# FiberLink.net
KiCad netlist of a schematic drawn in EAGLE
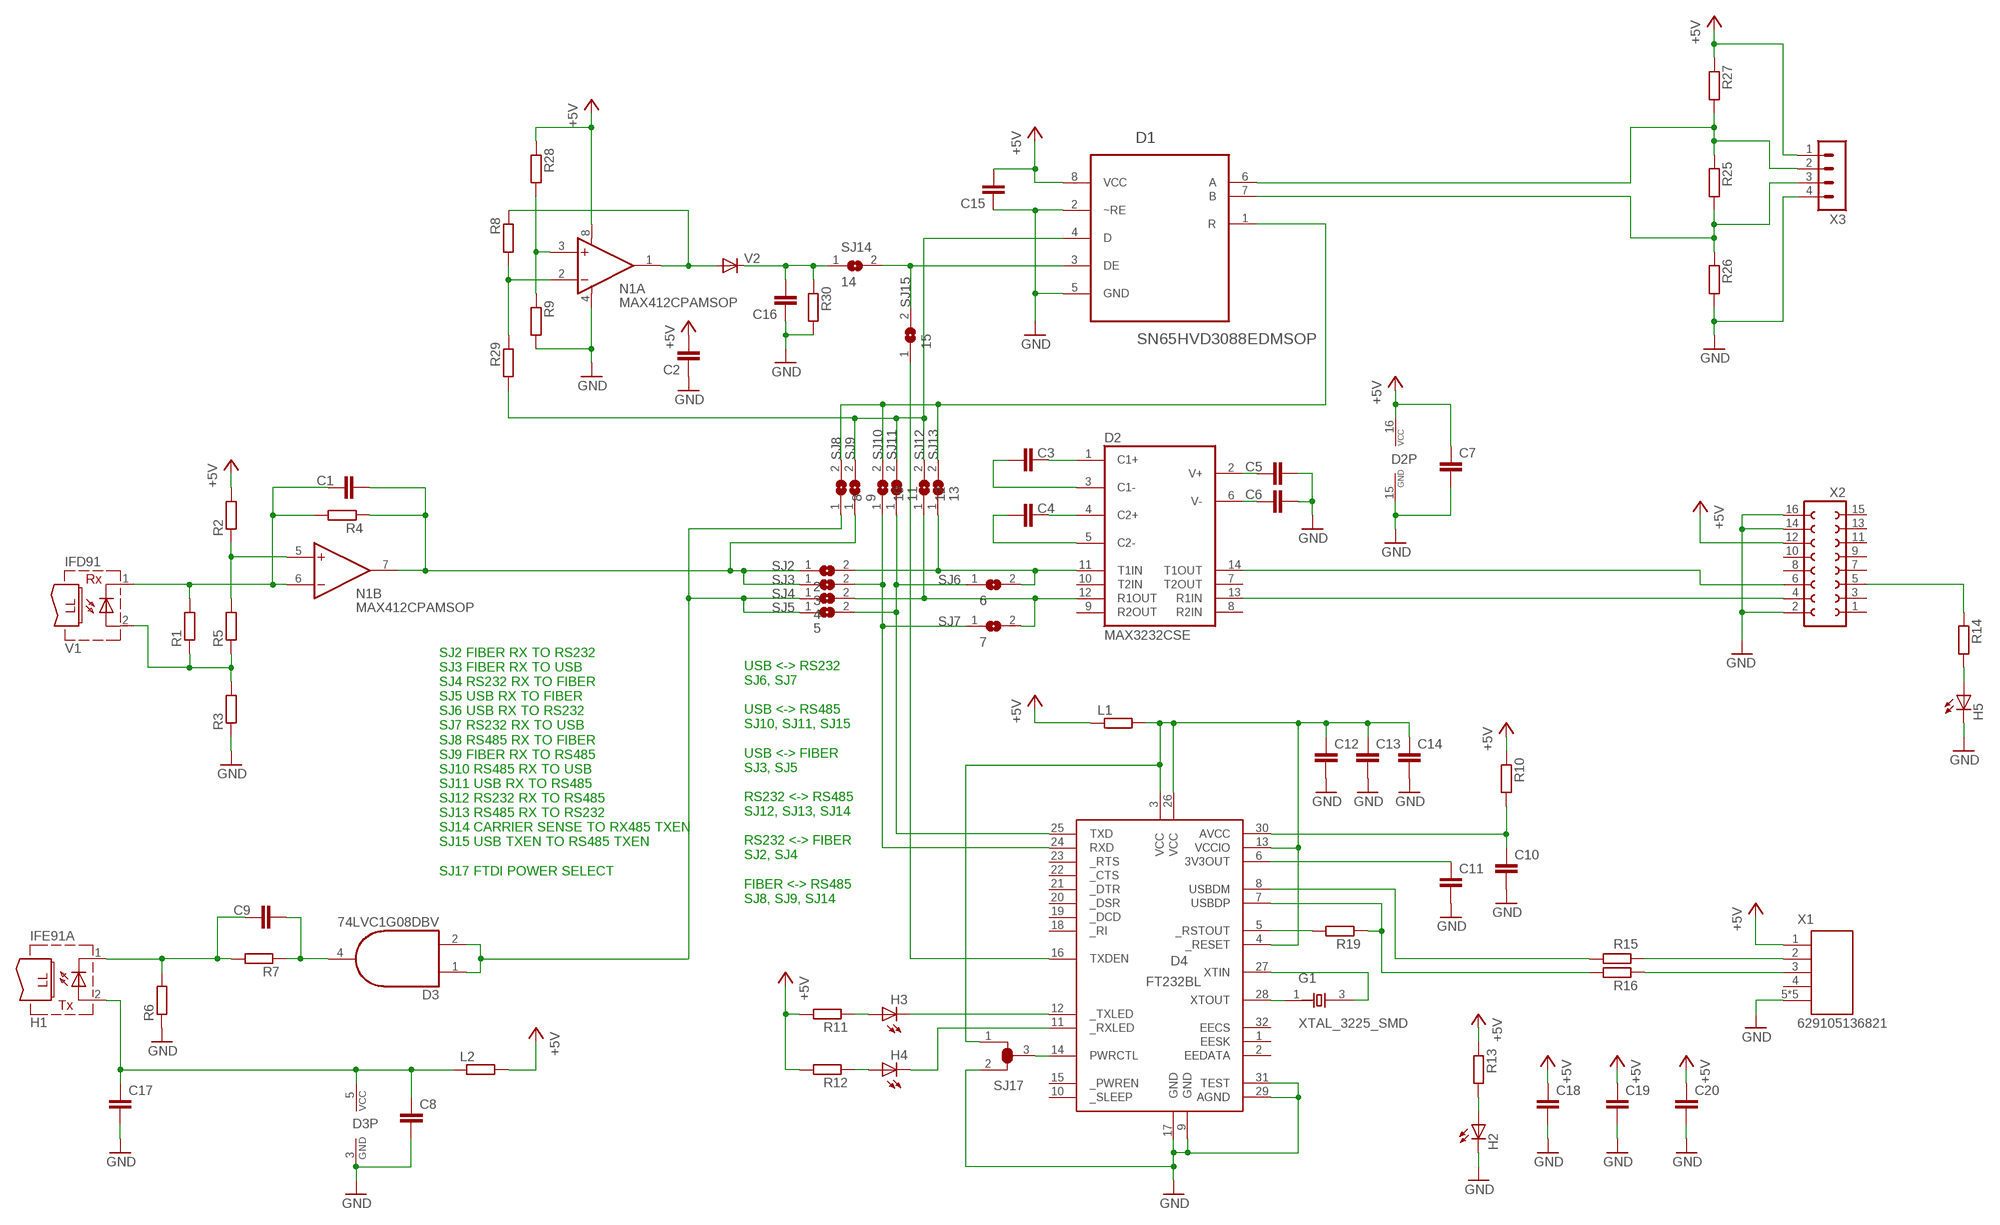
[diagram p0: schematic, sheet 1]

(export (version "E")
  (design (tool "Eeschema 10.0.6"))
  (components
    (comp (ref "C1")
      (value "C-EUC0402")
      (footprint "eagle-import:C0402")
      (libsource (lib "eagle-import") (part "C-EUC0402"))
    )
    (comp (ref "C2")
      (value "C-EUC0402")
      (footprint "eagle-import:C0402")
      (libsource (lib "eagle-import") (part "C-EUC0402"))
    )
    (comp (ref "C3")
      (value "C-EUC0402")
      (footprint "eagle-import:C0402")
      (libsource (lib "eagle-import") (part "C-EUC0402"))
    )
    (comp (ref "C4")
      (value "C-EUC0402")
      (footprint "eagle-import:C0402")
      (libsource (lib "eagle-import") (part "C-EUC0402"))
    )
    (comp (ref "C5")
      (value "C-EUC0402")
      (footprint "eagle-import:C0402")
      (libsource (lib "eagle-import") (part "C-EUC0402"))
    )
    (comp (ref "C6")
      (value "C-EUC0402")
      (footprint "eagle-import:C0402")
      (libsource (lib "eagle-import") (part "C-EUC0402"))
    )
    (comp (ref "C7")
      (value "C-EUC0402")
      (footprint "eagle-import:C0402")
      (libsource (lib "eagle-import") (part "C-EUC0402"))
    )
    (comp (ref "C8")
      (value "C-EUC0402")
      (footprint "eagle-import:C0402")
      (libsource (lib "eagle-import") (part "C-EUC0402"))
    )
    (comp (ref "C9")
      (value "C-EUC0402")
      (footprint "eagle-import:C0402")
      (libsource (lib "eagle-import") (part "C-EUC0402"))
    )
    (comp (ref "C10")
      (value "C-EUC0402")
      (footprint "eagle-import:C0402")
      (libsource (lib "eagle-import") (part "C-EUC0402"))
    )
    (comp (ref "C11")
      (value "C-EUC0402")
      (footprint "eagle-import:C0402")
      (libsource (lib "eagle-import") (part "C-EUC0402"))
    )
    (comp (ref "C12")
      (value "C-EUC0402")
      (footprint "eagle-import:C0402")
      (libsource (lib "eagle-import") (part "C-EUC0402"))
    )
    (comp (ref "C13")
      (value "C-EUC0402")
      (footprint "eagle-import:C0402")
      (libsource (lib "eagle-import") (part "C-EUC0402"))
    )
    (comp (ref "C14")
      (value "C-EUC0402")
      (footprint "eagle-import:C0402")
      (libsource (lib "eagle-import") (part "C-EUC0402"))
    )
    (comp (ref "C15")
      (value "C-EUC0402")
      (footprint "eagle-import:C0402")
      (libsource (lib "eagle-import") (part "C-EUC0402"))
    )
    (comp (ref "C16")
      (value "C-EUC0402")
      (footprint "eagle-import:C0402")
      (libsource (lib "eagle-import") (part "C-EUC0402"))
    )
    (comp (ref "C17")
      (value "C-EUC0402")
      (footprint "eagle-import:C0402")
      (libsource (lib "eagle-import") (part "C-EUC0402"))
    )
    (comp (ref "C18")
      (value "C-EUC0805")
      (footprint "eagle-import:C0805")
      (libsource (lib "eagle-import") (part "C-EUC0805"))
    )
    (comp (ref "C19")
      (value "C-EUC0805")
      (footprint "eagle-import:C0805")
      (libsource (lib "eagle-import") (part "C-EUC0805"))
    )
    (comp (ref "C20")
      (value "C-EUC0805")
      (footprint "eagle-import:C0805")
      (libsource (lib "eagle-import") (part "C-EUC0805"))
    )
    (comp (ref "D1")
      (value "SN65HVD3088EDMSOP")
      (footprint "eagle-import:SOP65P490X110-8N")
      (libsource (lib "eagle-import") (part "SN65HVD3088EDMSOP"))
    )
    (comp (ref "D2")
      (value "MAX3232CSE")
      (footprint "eagle-import:SO16")
      (libsource (lib "eagle-import") (part "MAX3232SEC"))
    )
    (comp (ref "D3")
      (value "74LVC1G08DBV")
      (footprint "eagle-import:SOT23-5")
      (libsource (lib "eagle-import") (part "741G08DBVLVC"))
    )
    (comp (ref "D4")
      (value "FT232BL")
      (footprint "eagle-import:LQFP32")
      (libsource (lib "eagle-import") (part "FT232BL"))
    )
    (comp (ref "G1")
      (value "XTAL_3225_SMD")
      (footprint "eagle-import:X_3225")
      (libsource (lib "eagle-import") (part "XTAL_3225_SMD"))
    )
    (comp (ref "H1")
      (value "IFE91A")
      (footprint "eagle-import:IFO-IFX")
      (libsource (lib "eagle-import") (part "IFE91A"))
    )
    (comp (ref "H2")
      (value "LEDCHIP-LED0603")
      (footprint "eagle-import:CHIP-LED0603")
      (libsource (lib "eagle-import") (part "LEDCHIP-LED0603"))
    )
    (comp (ref "H3")
      (value "LEDCHIP-LED0603")
      (footprint "eagle-import:CHIP-LED0603")
      (libsource (lib "eagle-import") (part "LEDCHIP-LED0603"))
    )
    (comp (ref "H4")
      (value "LEDCHIP-LED0603")
      (footprint "eagle-import:CHIP-LED0603")
      (libsource (lib "eagle-import") (part "LEDCHIP-LED0603"))
    )
    (comp (ref "H5")
      (value "LEDCHIP-LED0603")
      (footprint "eagle-import:CHIP-LED0603")
      (libsource (lib "eagle-import") (part "LEDCHIP-LED0603"))
    )
    (comp (ref "L1")
      (value "R-EU_R0402")
      (footprint "eagle-import:R0402_VISHAY")
      (libsource (lib "eagle-import") (part "R-EU_R0402"))
    )
    (comp (ref "L2")
      (value "R-EU_R0402")
      (footprint "eagle-import:R0402_VISHAY")
      (libsource (lib "eagle-import") (part "R-EU_R0402"))
    )
    (comp (ref "N1")
      (value "MAX412CPAMSOP")
      (footprint "eagle-import:SOP65P490X110-8N")
      (libsource (lib "eagle-import") (part "MAX412CPAMSOP"))
    )
    (comp (ref "R1")
      (value "R-EU_R0402")
      (footprint "eagle-import:R0402_VISHAY")
      (libsource (lib "eagle-import") (part "R-EU_R0402"))
    )
    (comp (ref "R2")
      (value "R-EU_R0402")
      (footprint "eagle-import:R0402_VISHAY")
      (libsource (lib "eagle-import") (part "R-EU_R0402"))
    )
    (comp (ref "R3")
      (value "R-EU_R0402")
      (footprint "eagle-import:R0402_VISHAY")
      (libsource (lib "eagle-import") (part "R-EU_R0402"))
    )
    (comp (ref "R4")
      (value "R-EU_R0402")
      (footprint "eagle-import:R0402_VISHAY")
      (libsource (lib "eagle-import") (part "R-EU_R0402"))
    )
    (comp (ref "R5")
      (value "R-EU_R0402")
      (footprint "eagle-import:R0402_VISHAY")
      (libsource (lib "eagle-import") (part "R-EU_R0402"))
    )
    (comp (ref "R6")
      (value "R-EU_R1206")
      (footprint "eagle-import:R1206")
      (libsource (lib "eagle-import") (part "R-EU_R1206"))
    )
    (comp (ref "R7")
      (value "R-EU_R1206")
      (footprint "eagle-import:R1206")
      (libsource (lib "eagle-import") (part "R-EU_R1206"))
    )
    (comp (ref "R8")
      (value "R-EU_R0402")
      (footprint "eagle-import:R0402_VISHAY")
      (libsource (lib "eagle-import") (part "R-EU_R0402"))
    )
    (comp (ref "R9")
      (value "R-EU_R0402")
      (footprint "eagle-import:R0402_VISHAY")
      (libsource (lib "eagle-import") (part "R-EU_R0402"))
    )
    (comp (ref "R10")
      (value "R-EU_R0402")
      (footprint "eagle-import:R0402_VISHAY")
      (libsource (lib "eagle-import") (part "R-EU_R0402"))
    )
    (comp (ref "R11")
      (value "R-EU_R0402")
      (footprint "eagle-import:R0402_VISHAY")
      (libsource (lib "eagle-import") (part "R-EU_R0402"))
    )
    (comp (ref "R12")
      (value "R-EU_R0402")
      (footprint "eagle-import:R0402_VISHAY")
      (libsource (lib "eagle-import") (part "R-EU_R0402"))
    )
    (comp (ref "R13")
      (value "R-EU_R0402")
      (footprint "eagle-import:R0402_VISHAY")
      (libsource (lib "eagle-import") (part "R-EU_R0402"))
    )
    (comp (ref "R14")
      (value "R-EU_R0402")
      (footprint "eagle-import:R0402_VISHAY")
      (libsource (lib "eagle-import") (part "R-EU_R0402"))
    )
    (comp (ref "R15")
      (value "R-EU_R0402")
      (footprint "eagle-import:R0402_VISHAY")
      (libsource (lib "eagle-import") (part "R-EU_R0402"))
    )
    (comp (ref "R16")
      (value "R-EU_R0402")
      (footprint "eagle-import:R0402_VISHAY")
      (libsource (lib "eagle-import") (part "R-EU_R0402"))
    )
    (comp (ref "R19")
      (value "R-EU_R0402")
      (footprint "eagle-import:R0402_VISHAY")
      (libsource (lib "eagle-import") (part "R-EU_R0402"))
    )
    (comp (ref "R25")
      (value "R-EU_R1206")
      (footprint "eagle-import:R1206")
      (libsource (lib "eagle-import") (part "R-EU_R1206"))
    )
    (comp (ref "R26")
      (value "R-EU_R0603")
      (footprint "eagle-import:R0603")
      (libsource (lib "eagle-import") (part "R-EU_R0603"))
    )
    (comp (ref "R27")
      (value "R-EU_R0603")
      (footprint "eagle-import:R0603")
      (libsource (lib "eagle-import") (part "R-EU_R0603"))
    )
    (comp (ref "R28")
      (value "R-EU_R0402")
      (footprint "eagle-import:R0402_VISHAY")
      (libsource (lib "eagle-import") (part "R-EU_R0402"))
    )
    (comp (ref "R29")
      (value "R-EU_R0402")
      (footprint "eagle-import:R0402_VISHAY")
      (libsource (lib "eagle-import") (part "R-EU_R0402"))
    )
    (comp (ref "R30")
      (value "R-EU_R0402")
      (footprint "eagle-import:R0402_VISHAY")
      (libsource (lib "eagle-import") (part "R-EU_R0402"))
    )
    (comp (ref "SJ2")
      (value "2")
      (footprint "eagle-import:SJ-SMALL")
      (libsource (lib "eagle-import") (part "SJ"))
    )
    (comp (ref "SJ3")
      (value "3")
      (footprint "eagle-import:SJ-SMALL")
      (libsource (lib "eagle-import") (part "SJ"))
    )
    (comp (ref "SJ4")
      (value "4")
      (footprint "eagle-import:SJ-SMALL")
      (libsource (lib "eagle-import") (part "SJ"))
    )
    (comp (ref "SJ5")
      (value "5")
      (footprint "eagle-import:SJ-SMALL")
      (libsource (lib "eagle-import") (part "SJ"))
    )
    (comp (ref "SJ6")
      (value "6")
      (footprint "eagle-import:SJ-SMALL")
      (libsource (lib "eagle-import") (part "SJ"))
    )
    (comp (ref "SJ7")
      (value "7")
      (footprint "eagle-import:SJ-SMALL")
      (libsource (lib "eagle-import") (part "SJ"))
    )
    (comp (ref "SJ8")
      (value "8")
      (footprint "eagle-import:SJ-SMALL")
      (libsource (lib "eagle-import") (part "SJ"))
    )
    (comp (ref "SJ9")
      (value "9")
      (footprint "eagle-import:SJ-SMALL")
      (libsource (lib "eagle-import") (part "SJ"))
    )
    (comp (ref "SJ10")
      (value "10")
      (footprint "eagle-import:SJ-SMALL")
      (libsource (lib "eagle-import") (part "SJ"))
    )
    (comp (ref "SJ11")
      (value "11")
      (footprint "eagle-import:SJ-SMALL")
      (libsource (lib "eagle-import") (part "SJ"))
    )
    (comp (ref "SJ12")
      (value "12")
      (footprint "eagle-import:SJ-SMALL")
      (libsource (lib "eagle-import") (part "SJ"))
    )
    (comp (ref "SJ13")
      (value "13")
      (footprint "eagle-import:SJ-SMALL")
      (libsource (lib "eagle-import") (part "SJ"))
    )
    (comp (ref "SJ14")
      (value "14")
      (footprint "eagle-import:SJ-SMALL")
      (libsource (lib "eagle-import") (part "SJ"))
    )
    (comp (ref "SJ15")
      (value "15")
      (footprint "eagle-import:SJ-SMALL")
      (libsource (lib "eagle-import") (part "SJ"))
    )
    (comp (ref "SJ17")
      (value "17")
      (footprint "eagle-import:SJ-SMALL-TRI")
      (libsource (lib "eagle-import") (part "SJ-TRI"))
    )
    (comp (ref "V1")
      (value "IFD91")
      (footprint "eagle-import:IFO-IFX")
      (libsource (lib "eagle-import") (part "IFD91"))
    )
    (comp (ref "V2")
      (value "DIODE-SOD323-R")
      (footprint "eagle-import:SOD323-R")
      (libsource (lib "eagle-import") (part "DIODE-SOD323-R"))
    )
    (comp (ref "X1")
      (value "629105136821")
      (footprint "eagle-import:629105136821")
      (libsource (lib "eagle-import") (part "629105136821"))
    )
    (comp (ref "X2")
      (value "FE08-2")
      (footprint "eagle-import:FE08-2")
      (libsource (lib "eagle-import") (part "FE08-2"))
    )
    (comp (ref "X3")
      (value "MA04-1")
      (footprint "eagle-import:MA04-1")
      (libsource (lib "eagle-import") (part "MA04-1"))
    )
  )
  (nets
    (net (code "1") (name "+5V") (class "Default")
      (node (ref "C15") (pin "2") (pinfunction "2_2") (pintype "passive"))
      (node (ref "C18") (pin "1") (pinfunction "1_1") (pintype "passive"))
      (node (ref "C19") (pin "1") (pinfunction "1_1") (pintype "passive"))
      (node (ref "C2") (pin "2") (pinfunction "2_2") (pintype "passive"))
      (node (ref "C20") (pin "1") (pinfunction "1_1") (pintype "passive"))
      (node (ref "C7") (pin "1") (pinfunction "1_1") (pintype "passive"))
      (node (ref "D1") (pin "8") (pinfunction "VCC_8") (pintype "power_in"))
      (node (ref "D2") (pin "16") (pinfunction "VCC_16") (pintype "power_in"))
      (node (ref "L1") (pin "1") (pinfunction "1_1") (pintype "passive"))
      (node (ref "L2") (pin "2") (pinfunction "2_2") (pintype "passive"))
      (node (ref "N1") (pin "8") (pinfunction "V+_8") (pintype "power_in"))
      (node (ref "R10") (pin "1") (pinfunction "1_1") (pintype "passive"))
      (node (ref "R11") (pin "2") (pinfunction "2_2") (pintype "passive"))
      (node (ref "R12") (pin "2") (pinfunction "2_2") (pintype "passive"))
      (node (ref "R13") (pin "1") (pinfunction "1_1") (pintype "passive"))
      (node (ref "R2") (pin "2") (pinfunction "2_2") (pintype "passive"))
      (node (ref "R27") (pin "1") (pinfunction "1_1") (pintype "passive"))
      (node (ref "R28") (pin "1") (pinfunction "1_1") (pintype "passive"))
      (node (ref "X1") (pin "1") (pinfunction "1_1") (pintype "passive"))
      (node (ref "X2") (pin "12") (pinfunction "12_12") (pintype "passive"))
      (node (ref "X3") (pin "1") (pinfunction "1_1") (pintype "passive"))
    )
    (net (code "2") (name "GND") (class "Default")
      (node (ref "C10") (pin "2") (pinfunction "2_2") (pintype "passive"))
      (node (ref "C11") (pin "2") (pinfunction "2_2") (pintype "passive"))
      (node (ref "C12") (pin "2") (pinfunction "2_2") (pintype "passive"))
      (node (ref "C13") (pin "2") (pinfunction "2_2") (pintype "passive"))
      (node (ref "C14") (pin "2") (pinfunction "2_2") (pintype "passive"))
      (node (ref "C15") (pin "1") (pinfunction "1_1") (pintype "passive"))
      (node (ref "C16") (pin "1") (pinfunction "1_1") (pintype "passive"))
      (node (ref "C17") (pin "2") (pinfunction "2_2") (pintype "passive"))
      (node (ref "C18") (pin "2") (pinfunction "2_2") (pintype "passive"))
      (node (ref "C19") (pin "2") (pinfunction "2_2") (pintype "passive"))
      (node (ref "C2") (pin "1") (pinfunction "1_1") (pintype "passive"))
      (node (ref "C20") (pin "2") (pinfunction "2_2") (pintype "passive"))
      (node (ref "C5") (pin "2") (pinfunction "2_2") (pintype "passive"))
      (node (ref "C6") (pin "2") (pinfunction "2_2") (pintype "passive"))
      (node (ref "C7") (pin "2") (pinfunction "2_2") (pintype "passive"))
      (node (ref "C8") (pin "2") (pinfunction "2_2") (pintype "passive"))
      (node (ref "D1") (pin "2") (pinfunction "~{RE}_2") (pintype "input"))
      (node (ref "D1") (pin "5") (pinfunction "GND_5") (pintype "passive"))
      (node (ref "D2") (pin "15") (pinfunction "GND_15") (pintype "power_in"))
      (node (ref "D3") (pin "3") (pinfunction "GND_3") (pintype "power_in"))
      (node (ref "D4") (pin "17") (pinfunction "GND_17") (pintype "power_in"))
      (node (ref "D4") (pin "29") (pinfunction "AGND_29") (pintype "power_in"))
      (node (ref "D4") (pin "31") (pinfunction "TEST_31") (pintype "input"))
      (node (ref "D4") (pin "9") (pinfunction "GND_9") (pintype "power_in"))
      (node (ref "H2") (pin "C") (pinfunction "C_C") (pintype "passive"))
      (node (ref "H5") (pin "C") (pinfunction "C_C") (pintype "passive"))
      (node (ref "N1") (pin "4") (pinfunction "V-_4") (pintype "power_in"))
      (node (ref "R26") (pin "2") (pinfunction "2_2") (pintype "passive"))
      (node (ref "R3") (pin "1") (pinfunction "1_1") (pintype "passive"))
      (node (ref "R30") (pin "2") (pinfunction "2_2") (pintype "passive"))
      (node (ref "R6") (pin "1") (pinfunction "1_1") (pintype "passive"))
      (node (ref "R9") (pin "2") (pinfunction "2_2") (pintype "passive"))
      (node (ref "SJ17") (pin "2") (pinfunction "2_2") (pintype "passive"))
      (node (ref "X1") (pin "5") (pinfunction "5_5") (pintype "passive"))
      (node (ref "X1") (pin "Z1") (pinfunction "5_Z1") (pintype "passive"))
      (node (ref "X1") (pin "Z2") (pinfunction "5_Z2") (pintype "passive"))
      (node (ref "X1") (pin "Z3") (pinfunction "5_Z3") (pintype "passive"))
      (node (ref "X1") (pin "Z4") (pinfunction "5_Z4") (pintype "passive"))
      (node (ref "X2") (pin "14") (pinfunction "14_14") (pintype "passive"))
      (node (ref "X2") (pin "16") (pinfunction "16_16") (pintype "passive"))
      (node (ref "X2") (pin "2") (pinfunction "2_2") (pintype "passive"))
      (node (ref "X3") (pin "4") (pinfunction "4_4") (pintype "passive"))
    )
    (net (code "3") (name "Net-(C16-Pad2)") (class "Default")
      (node (ref "C16") (pin "2") (pinfunction "2_2") (pintype "passive"))
      (node (ref "R30") (pin "1") (pinfunction "1_1") (pintype "passive"))
      (node (ref "SJ14") (pin "1") (pinfunction "1_1") (pintype "passive"))
      (node (ref "V2") (pin "C") (pinfunction "C_C") (pintype "passive"))
    )
    (net (code "4") (name "Net-(D1-A)") (class "Default")
      (node (ref "D1") (pin "6") (pinfunction "A_6") (pintype "output"))
      (node (ref "R25") (pin "1") (pinfunction "1_1") (pintype "passive"))
      (node (ref "R27") (pin "2") (pinfunction "2_2") (pintype "passive"))
      (node (ref "X3") (pin "2") (pinfunction "2_2") (pintype "passive"))
    )
    (net (code "5") (name "Net-(D1-B)") (class "Default")
      (node (ref "D1") (pin "7") (pinfunction "B_7") (pintype "output"))
      (node (ref "R25") (pin "2") (pinfunction "2_2") (pintype "passive"))
      (node (ref "R26") (pin "1") (pinfunction "1_1") (pintype "passive"))
      (node (ref "X3") (pin "3") (pinfunction "3_3") (pintype "passive"))
    )
    (net (code "6") (name "Net-(D1-D)") (class "Default")
      (node (ref "D1") (pin "4") (pinfunction "D_4") (pintype "input"))
      (node (ref "R29") (pin "2") (pinfunction "2_2") (pintype "passive"))
      (node (ref "SJ11") (pin "2") (pinfunction "2_2") (pintype "passive"))
      (node (ref "SJ12") (pin "2") (pinfunction "2_2") (pintype "passive"))
      (node (ref "SJ9") (pin "2") (pinfunction "2_2") (pintype "passive"))
    )
    (net (code "7") (name "Net-(D1-DE)") (class "Default")
      (node (ref "D1") (pin "3") (pinfunction "DE_3") (pintype "input"))
      (node (ref "SJ14") (pin "2") (pinfunction "2_2") (pintype "passive"))
      (node (ref "SJ15") (pin "2") (pinfunction "2_2") (pintype "passive"))
    )
    (net (code "8") (name "Net-(D1-R)") (class "Default")
      (node (ref "D1") (pin "1") (pinfunction "R_1") (pintype "output"))
      (node (ref "SJ10") (pin "2") (pinfunction "2_2") (pintype "passive"))
      (node (ref "SJ13") (pin "2") (pinfunction "2_2") (pintype "passive"))
      (node (ref "SJ8") (pin "2") (pinfunction "2_2") (pintype "passive"))
    )
    (net (code "9") (name "Net-(D2A-C1+)") (class "Default")
      (node (ref "C3") (pin "1") (pinfunction "1_1") (pintype "passive"))
      (node (ref "D2") (pin "1") (pinfunction "C1+_1") (pintype "bidirectional"))
    )
    (net (code "10") (name "Net-(D2A-C1-)") (class "Default")
      (node (ref "C3") (pin "2") (pinfunction "2_2") (pintype "passive"))
      (node (ref "D2") (pin "3") (pinfunction "C1-_3") (pintype "bidirectional"))
    )
    (net (code "11") (name "Net-(D2A-C2+)") (class "Default")
      (node (ref "C4") (pin "1") (pinfunction "1_1") (pintype "passive"))
      (node (ref "D2") (pin "4") (pinfunction "C2+_4") (pintype "bidirectional"))
    )
    (net (code "12") (name "Net-(D2A-C2-)") (class "Default")
      (node (ref "C4") (pin "2") (pinfunction "2_2") (pintype "passive"))
      (node (ref "D2") (pin "5") (pinfunction "C2-_5") (pintype "bidirectional"))
    )
    (net (code "13") (name "Net-(D2A-R1IN)") (class "Default")
      (node (ref "D2") (pin "13") (pinfunction "R1IN_13") (pintype "input"))
      (node (ref "X2") (pin "4") (pinfunction "4_4") (pintype "passive"))
    )
    (net (code "14") (name "Net-(D2A-R1OUT)") (class "Default")
      (node (ref "D2") (pin "12") (pinfunction "R1OUT_12") (pintype "output"))
      (node (ref "SJ12") (pin "1") (pinfunction "1_1") (pintype "passive"))
      (node (ref "SJ4") (pin "2") (pinfunction "2_2") (pintype "passive"))
      (node (ref "SJ7") (pin "2") (pinfunction "2_2") (pintype "passive"))
    )
    (net (code "15") (name "Net-(D2A-T1IN)") (class "Default")
      (node (ref "D2") (pin "11") (pinfunction "T1IN_11") (pintype "input"))
      (node (ref "SJ13") (pin "1") (pinfunction "1_1") (pintype "passive"))
      (node (ref "SJ2") (pin "2") (pinfunction "2_2") (pintype "passive"))
      (node (ref "SJ6") (pin "2") (pinfunction "2_2") (pintype "passive"))
    )
    (net (code "16") (name "Net-(D2A-T1OUT)") (class "Default")
      (node (ref "D2") (pin "14") (pinfunction "T1OUT_14") (pintype "output"))
      (node (ref "X2") (pin "6") (pinfunction "6_6") (pintype "passive"))
    )
    (net (code "17") (name "Net-(D2A-V+)") (class "Default")
      (node (ref "C5") (pin "1") (pinfunction "1_1") (pintype "passive"))
      (node (ref "D2") (pin "2") (pinfunction "V+_2") (pintype "bidirectional"))
    )
    (net (code "18") (name "Net-(D2A-V-)") (class "Default")
      (node (ref "C6") (pin "1") (pinfunction "1_1") (pintype "passive"))
      (node (ref "D2") (pin "6") (pinfunction "V-_6") (pintype "bidirectional"))
    )
    (net (code "19") (name "Net-(D3A-I0)") (class "Default")
      (node (ref "D3") (pin "1") (pinfunction "I0_1") (pintype "input"))
      (node (ref "D3") (pin "2") (pinfunction "I1_2") (pintype "input"))
      (node (ref "SJ4") (pin "1") (pinfunction "1_1") (pintype "passive"))
      (node (ref "SJ5") (pin "1") (pinfunction "1_1") (pintype "passive"))
      (node (ref "SJ8") (pin "1") (pinfunction "1_1") (pintype "passive"))
    )
    (net (code "20") (name "Net-(D3A-O)") (class "Default")
      (node (ref "C9") (pin "2") (pinfunction "2_2") (pintype "passive"))
      (node (ref "D3") (pin "4") (pinfunction "O_4") (pintype "output"))
      (node (ref "R7") (pin "1") (pinfunction "1_1") (pintype "passive"))
    )
    (net (code "21") (name "Net-(D3B-VCC)") (class "Default")
      (node (ref "C17") (pin "1") (pinfunction "1_1") (pintype "passive"))
      (node (ref "C8") (pin "1") (pinfunction "1_1") (pintype "passive"))
      (node (ref "D3") (pin "5") (pinfunction "VCC_5") (pintype "power_in"))
      (node (ref "H1") (pin "2") (pinfunction "A_2") (pintype "passive"))
      (node (ref "L2") (pin "1") (pinfunction "1_1") (pintype "passive"))
    )
    (net (code "22") (name "Net-(D4-3V3OUT)") (class "Default")
      (node (ref "C11") (pin "1") (pinfunction "1_1") (pintype "passive"))
      (node (ref "D4") (pin "6") (pinfunction "3V3OUT_6") (pintype "output"))
    )
    (net (code "23") (name "Net-(D4-AVCC)") (class "Default")
      (node (ref "C10") (pin "1") (pinfunction "1_1") (pintype "passive"))
      (node (ref "D4") (pin "30") (pinfunction "AVCC_30") (pintype "power_in"))
      (node (ref "R10") (pin "2") (pinfunction "2_2") (pintype "passive"))
    )
    (net (code "24") (name "Net-(D4-PWRCTL)") (class "Default")
      (node (ref "D4") (pin "14") (pinfunction "PWRCTL_14") (pintype "input"))
      (node (ref "SJ17") (pin "3") (pinfunction "3_3") (pintype "passive"))
    )
    (net (code "25") (name "Net-(D4-RXD)") (class "Default")
      (node (ref "D4") (pin "24") (pinfunction "RXD_24") (pintype "input"))
      (node (ref "SJ10") (pin "1") (pinfunction "1_1") (pintype "passive"))
      (node (ref "SJ3") (pin "2") (pinfunction "2_2") (pintype "passive"))
      (node (ref "SJ7") (pin "1") (pinfunction "1_1") (pintype "passive"))
    )
    (net (code "26") (name "Net-(D4-TXD)") (class "Default")
      (node (ref "D4") (pin "25") (pinfunction "TXD_25") (pintype "output"))
      (node (ref "SJ11") (pin "1") (pinfunction "1_1") (pintype "passive"))
      (node (ref "SJ5") (pin "2") (pinfunction "2_2") (pintype "passive"))
      (node (ref "SJ6") (pin "1") (pinfunction "1_1") (pintype "passive"))
    )
    (net (code "27") (name "Net-(D4-TXDEN)") (class "Default")
      (node (ref "D4") (pin "16") (pinfunction "TXDEN_16") (pintype "output"))
      (node (ref "SJ15") (pin "1") (pinfunction "1_1") (pintype "passive"))
    )
    (net (code "28") (name "Net-(D4-USBDM)") (class "Default")
      (node (ref "D4") (pin "8") (pinfunction "USBDM_8") (pintype "bidirectional"))
      (node (ref "R15") (pin "2") (pinfunction "2_2") (pintype "passive"))
    )
    (net (code "29") (name "Net-(D4-USBDP)") (class "Default")
      (node (ref "D4") (pin "7") (pinfunction "USBDP_7") (pintype "bidirectional"))
      (node (ref "R16") (pin "2") (pinfunction "2_2") (pintype "passive"))
      (node (ref "R19") (pin "1") (pinfunction "1_1") (pintype "passive"))
    )
    (net (code "30") (name "Net-(D4-VCCIO)") (class "Default")
      (node (ref "C12") (pin "1") (pinfunction "1_1") (pintype "passive"))
      (node (ref "C13") (pin "1") (pinfunction "1_1") (pintype "passive"))
      (node (ref "C14") (pin "1") (pinfunction "1_1") (pintype "passive"))
      (node (ref "D4") (pin "13") (pinfunction "VCCIO_13") (pintype "power_in"))
      (node (ref "D4") (pin "26") (pinfunction "VCC_26") (pintype "power_in"))
      (node (ref "D4") (pin "3") (pinfunction "VCC_3") (pintype "power_in"))
      (node (ref "D4") (pin "4") (pinfunction "_RESET_4") (pintype "input"))
      (node (ref "L1") (pin "2") (pinfunction "2_2") (pintype "passive"))
      (node (ref "SJ17") (pin "1") (pinfunction "1_1") (pintype "passive"))
    )
    (net (code "31") (name "Net-(D4-XTIN)") (class "Default")
      (node (ref "D4") (pin "27") (pinfunction "XTIN_27") (pintype "input"))
      (node (ref "G1") (pin "3") (pinfunction "X2_3") (pintype "bidirectional"))
    )
    (net (code "32") (name "Net-(D4-XTOUT)") (class "Default")
      (node (ref "D4") (pin "28") (pinfunction "XTOUT_28") (pintype "output"))
      (node (ref "G1") (pin "1") (pinfunction "X1_1") (pintype "bidirectional"))
    )
    (net (code "33") (name "Net-(D4-_RSTOUT)") (class "Default")
      (node (ref "D4") (pin "5") (pinfunction "_RSTOUT_5") (pintype "output"))
      (node (ref "R19") (pin "2") (pinfunction "2_2") (pintype "passive"))
    )
    (net (code "34") (name "Net-(D4-_RXLED)") (class "Default")
      (node (ref "D4") (pin "11") (pinfunction "_RXLED_11") (pintype "open_collector"))
      (node (ref "H4") (pin "C") (pinfunction "C_C") (pintype "passive"))
    )
    (net (code "35") (name "Net-(D4-_TXLED)") (class "Default")
      (node (ref "D4") (pin "12") (pinfunction "_TXLED_12") (pintype "open_collector"))
      (node (ref "H3") (pin "C") (pinfunction "C_C") (pintype "passive"))
    )
    (net (code "36") (name "Net-(H1-C)") (class "Default")
      (node (ref "C9") (pin "1") (pinfunction "1_1") (pintype "passive"))
      (node (ref "H1") (pin "1") (pinfunction "C_1") (pintype "passive"))
      (node (ref "R6") (pin "2") (pinfunction "2_2") (pintype "passive"))
      (node (ref "R7") (pin "2") (pinfunction "2_2") (pintype "passive"))
    )
    (net (code "37") (name "Net-(H2-PadA)") (class "Default")
      (node (ref "H2") (pin "A") (pinfunction "A_A") (pintype "passive"))
      (node (ref "R13") (pin "2") (pinfunction "2_2") (pintype "passive"))
    )
    (net (code "38") (name "Net-(H3-PadA)") (class "Default")
      (node (ref "H3") (pin "A") (pinfunction "A_A") (pintype "passive"))
      (node (ref "R11") (pin "1") (pinfunction "1_1") (pintype "passive"))
    )
    (net (code "39") (name "Net-(H4-PadA)") (class "Default")
      (node (ref "H4") (pin "A") (pinfunction "A_A") (pintype "passive"))
      (node (ref "R12") (pin "1") (pinfunction "1_1") (pintype "passive"))
    )
    (net (code "40") (name "Net-(H5-PadA)") (class "Default")
      (node (ref "H5") (pin "A") (pinfunction "A_A") (pintype "passive"))
      (node (ref "R14") (pin "2") (pinfunction "2_2") (pintype "passive"))
    )
    (net (code "41") (name "Net-(N1A-+IN)") (class "Default")
      (node (ref "N1") (pin "3") (pinfunction "+IN_3") (pintype "input"))
      (node (ref "R28") (pin "2") (pinfunction "2_2") (pintype "passive"))
      (node (ref "R9") (pin "1") (pinfunction "1_1") (pintype "passive"))
    )
    (net (code "42") (name "Net-(N1A--IN)") (class "Default")
      (node (ref "N1") (pin "2") (pinfunction "-IN_2") (pintype "input"))
      (node (ref "R29") (pin "1") (pinfunction "1_1") (pintype "passive"))
      (node (ref "R8") (pin "2") (pinfunction "2_2") (pintype "passive"))
    )
    (net (code "43") (name "Net-(N1A-OUT)") (class "Default")
      (node (ref "N1") (pin "1") (pinfunction "OUT_1") (pintype "output"))
      (node (ref "R8") (pin "1") (pinfunction "1_1") (pintype "passive"))
      (node (ref "V2") (pin "A") (pinfunction "A_A") (pintype "passive"))
    )
    (net (code "44") (name "Net-(N1B-+IN)") (class "Default")
      (node (ref "N1") (pin "5") (pinfunction "+IN_5") (pintype "input"))
      (node (ref "R2") (pin "1") (pinfunction "1_1") (pintype "passive"))
      (node (ref "R5") (pin "2") (pinfunction "2_2") (pintype "passive"))
    )
    (net (code "45") (name "Net-(N1B--IN)") (class "Default")
      (node (ref "C1") (pin "1") (pinfunction "1_1") (pintype "passive"))
      (node (ref "N1") (pin "6") (pinfunction "-IN_6") (pintype "input"))
      (node (ref "R1") (pin "2") (pinfunction "2_2") (pintype "passive"))
      (node (ref "R4") (pin "2") (pinfunction "2_2") (pintype "passive"))
      (node (ref "V1") (pin "1") (pinfunction "C_1") (pintype "passive"))
    )
    (net (code "46") (name "Net-(N1B-OUT)") (class "Default")
      (node (ref "C1") (pin "2") (pinfunction "2_2") (pintype "passive"))
      (node (ref "N1") (pin "7") (pinfunction "OUT_7") (pintype "output"))
      (node (ref "R4") (pin "1") (pinfunction "1_1") (pintype "passive"))
      (node (ref "SJ2") (pin "1") (pinfunction "1_1") (pintype "passive"))
      (node (ref "SJ3") (pin "1") (pinfunction "1_1") (pintype "passive"))
      (node (ref "SJ9") (pin "1") (pinfunction "1_1") (pintype "passive"))
    )
    (net (code "47") (name "Net-(R14-Pad1)") (class "Default")
      (node (ref "R14") (pin "1") (pinfunction "1_1") (pintype "passive"))
      (node (ref "X2") (pin "5") (pinfunction "5_5") (pintype "passive"))
    )
    (net (code "48") (name "Net-(R15-Pad1)") (class "Default")
      (node (ref "R15") (pin "1") (pinfunction "1_1") (pintype "passive"))
      (node (ref "X1") (pin "2") (pinfunction "2_2") (pintype "passive"))
    )
    (net (code "49") (name "Net-(R16-Pad1)") (class "Default")
      (node (ref "R16") (pin "1") (pinfunction "1_1") (pintype "passive"))
      (node (ref "X1") (pin "3") (pinfunction "3_3") (pintype "passive"))
    )
    (net (code "50") (name "Net-(V1-A)") (class "Default")
      (node (ref "R1") (pin "1") (pinfunction "1_1") (pintype "passive"))
      (node (ref "R3") (pin "2") (pinfunction "2_2") (pintype "passive"))
      (node (ref "R5") (pin "1") (pinfunction "1_1") (pintype "passive"))
      (node (ref "V1") (pin "2") (pinfunction "A_2") (pintype "passive"))
    )
    (net (code "51") (name "unconnected-(D2A-R2IN-Pad8)") (class "Default")
      (node (ref "D2") (pin "8") (pinfunction "R2IN_8") (pintype "input"))
    )
    (net (code "52") (name "unconnected-(D2A-R2OUT-Pad9)") (class "Default")
      (node (ref "D2") (pin "9") (pinfunction "R2OUT_9") (pintype "output"))
    )
    (net (code "53") (name "unconnected-(D2A-T2IN-Pad10)") (class "Default")
      (node (ref "D2") (pin "10") (pinfunction "T2IN_10") (pintype "input"))
    )
    (net (code "54") (name "unconnected-(D2A-T2OUT-Pad7)") (class "Default")
      (node (ref "D2") (pin "7") (pinfunction "T2OUT_7") (pintype "output"))
    )
    (net (code "55") (name "unconnected-(D4-EECS-Pad32)") (class "Default")
      (node (ref "D4") (pin "32") (pinfunction "EECS_32") (pintype "bidirectional"))
    )
    (net (code "56") (name "unconnected-(D4-EEDATA-Pad2)") (class "Default")
      (node (ref "D4") (pin "2") (pinfunction "EEDATA_2") (pintype "bidirectional"))
    )
    (net (code "57") (name "unconnected-(D4-EESK-Pad1)") (class "Default")
      (node (ref "D4") (pin "1") (pinfunction "EESK_1") (pintype "output"))
    )
    (net (code "58") (name "unconnected-(D4-_CTS-Pad22)") (class "Default")
      (node (ref "D4") (pin "22") (pinfunction "_CTS_22") (pintype "input"))
    )
    (net (code "59") (name "unconnected-(D4-_DCD-Pad19)") (class "Default")
      (node (ref "D4") (pin "19") (pinfunction "_DCD_19") (pintype "input"))
    )
    (net (code "60") (name "unconnected-(D4-_DSR-Pad20)") (class "Default")
      (node (ref "D4") (pin "20") (pinfunction "_DSR_20") (pintype "input"))
    )
    (net (code "61") (name "unconnected-(D4-_DTR-Pad21)") (class "Default")
      (node (ref "D4") (pin "21") (pinfunction "_DTR_21") (pintype "output"))
    )
    (net (code "62") (name "unconnected-(D4-_PWREN-Pad15)") (class "Default")
      (node (ref "D4") (pin "15") (pinfunction "_PWREN_15") (pintype "output"))
    )
    (net (code "63") (name "unconnected-(D4-_RI-Pad18)") (class "Default")
      (node (ref "D4") (pin "18") (pinfunction "_RI_18") (pintype "input"))
    )
    (net (code "64") (name "unconnected-(D4-_RTS-Pad23)") (class "Default")
      (node (ref "D4") (pin "23") (pinfunction "_RTS_23") (pintype "output"))
    )
    (net (code "65") (name "unconnected-(D4-_SLEEP-Pad10)") (class "Default")
      (node (ref "D4") (pin "10") (pinfunction "_SLEEP_10") (pintype "output"))
    )
    (net (code "66") (name "unconnected-(X1-Pad4)") (class "Default")
      (node (ref "X1") (pin "4") (pinfunction "4_4") (pintype "passive"))
    )
    (net (code "67") (name "unconnected-(X2-Pad1)") (class "Default")
      (node (ref "X2") (pin "1") (pinfunction "1_1") (pintype "passive"))
    )
    (net (code "68") (name "unconnected-(X2-Pad3)") (class "Default")
      (node (ref "X2") (pin "3") (pinfunction "3_3") (pintype "passive"))
    )
    (net (code "69") (name "unconnected-(X2-Pad7)") (class "Default")
      (node (ref "X2") (pin "7") (pinfunction "7_7") (pintype "passive"))
    )
    (net (code "70") (name "unconnected-(X2-Pad8)") (class "Default")
      (node (ref "X2") (pin "8") (pinfunction "8_8") (pintype "passive"))
    )
    (net (code "71") (name "unconnected-(X2-Pad9)") (class "Default")
      (node (ref "X2") (pin "9") (pinfunction "9_9") (pintype "passive"))
    )
    (net (code "72") (name "unconnected-(X2-Pad10)") (class "Default")
      (node (ref "X2") (pin "10") (pinfunction "10_10") (pintype "passive"))
    )
    (net (code "73") (name "unconnected-(X2-Pad11)") (class "Default")
      (node (ref "X2") (pin "11") (pinfunction "11_11") (pintype "passive"))
    )
    (net (code "74") (name "unconnected-(X2-Pad13)") (class "Default")
      (node (ref "X2") (pin "13") (pinfunction "13_13") (pintype "passive"))
    )
    (net (code "75") (name "unconnected-(X2-Pad15)") (class "Default")
      (node (ref "X2") (pin "15") (pinfunction "15_15") (pintype "passive"))
    )
  )
)
